# atlas_double.net
KiCad netlist of a schematic drawn in EAGLE
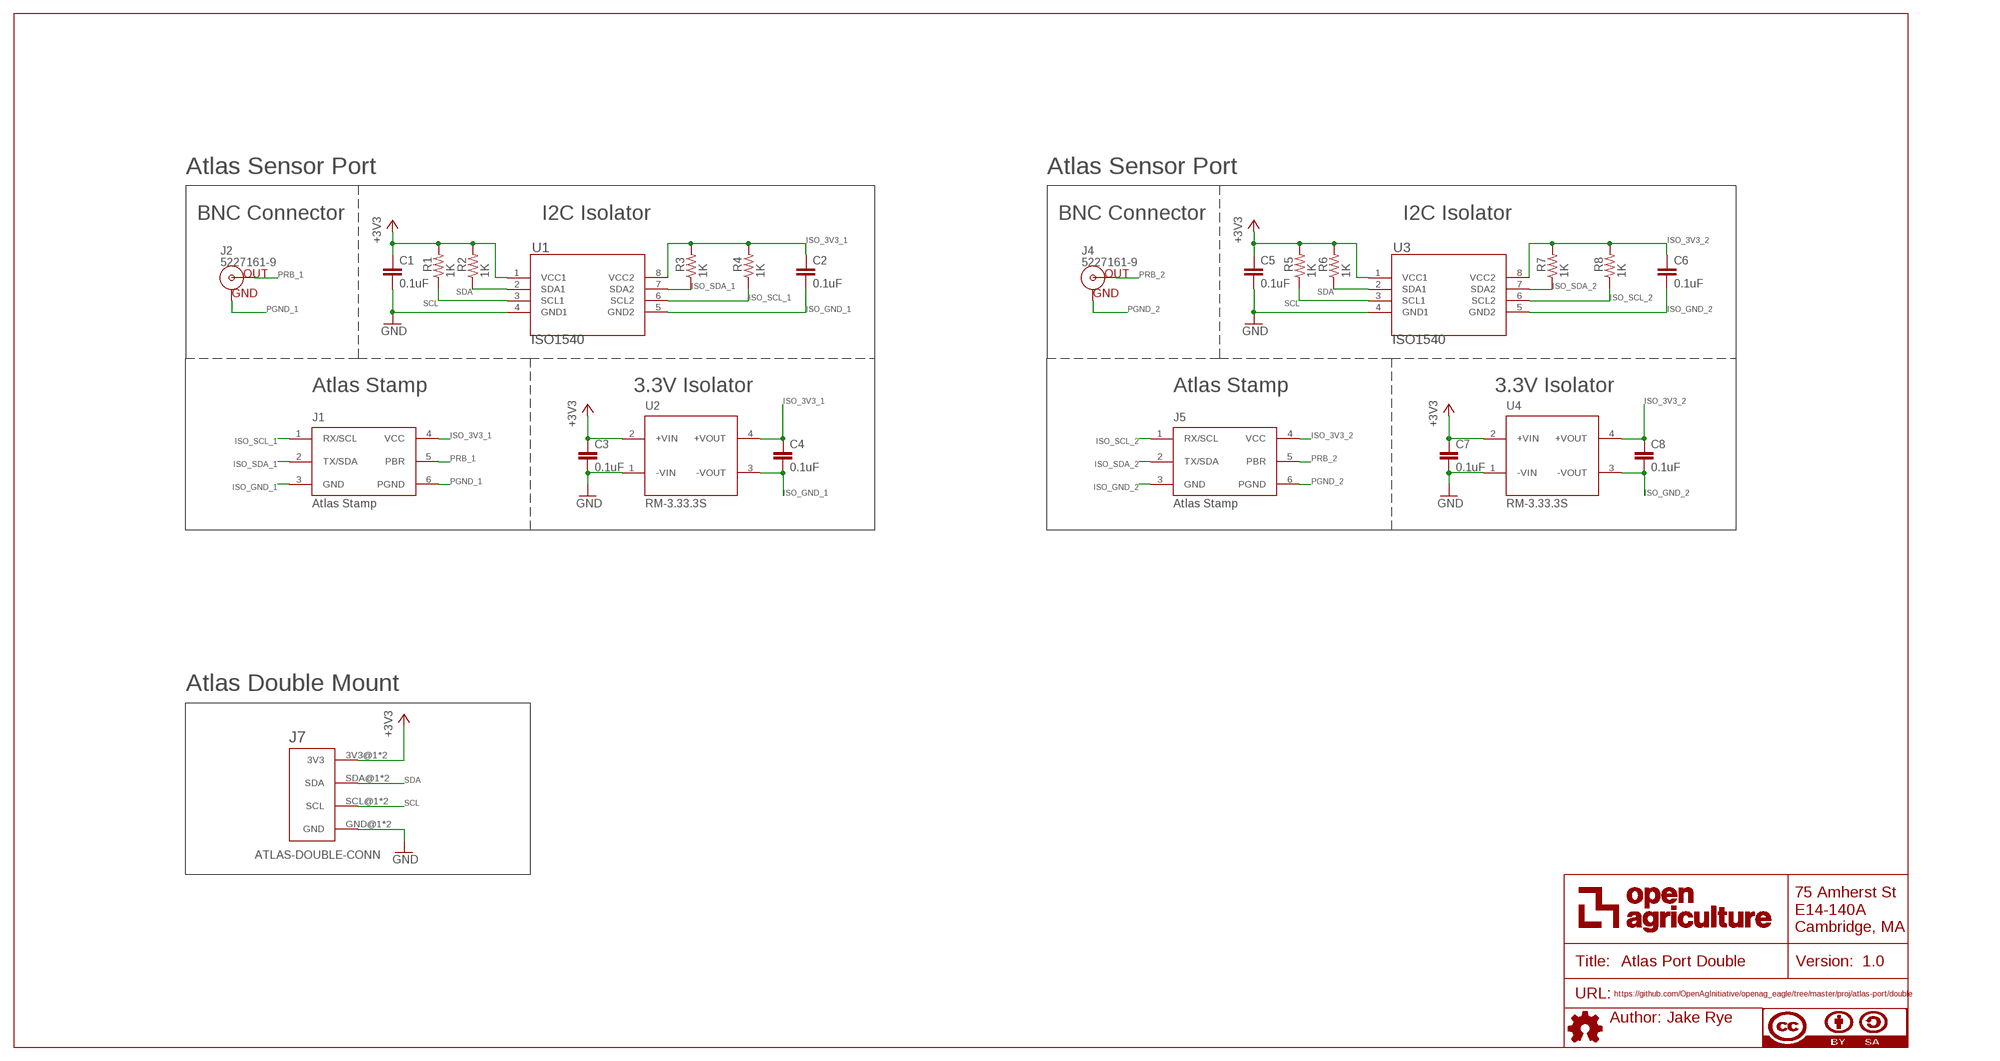
[diagram p0: schematic, sheet 1]

(export (version "E")
  (design (tool "Eeschema 10.0.6"))
  (components
    (comp (ref "C1")
      (value "0.1uF")
      (footprint "eagle-import:C0603")
      (fields (field (name "MANUFACTURER") "Kemet") (field (name "MPN") "C0603C104K5RACTU"))
      (libsource (lib "eagle-import") (part "0.1UF-C0603C104K5RACTU"))
    )
    (comp (ref "C2")
      (value "0.1uF")
      (footprint "eagle-import:C0603")
      (fields (field (name "MANUFACTURER") "Kemet") (field (name "MPN") "C0603C104K5RACTU"))
      (libsource (lib "eagle-import") (part "0.1UF-C0603C104K5RACTU"))
    )
    (comp (ref "C3")
      (value "0.1uF")
      (footprint "eagle-import:C0603")
      (fields (field (name "MANUFACTURER") "Kemet") (field (name "MPN") "C0603C104K5RACTU"))
      (libsource (lib "eagle-import") (part "0.1UF-C0603C104K5RACTU"))
    )
    (comp (ref "C4")
      (value "0.1uF")
      (footprint "eagle-import:C0603")
      (fields (field (name "MANUFACTURER") "Kemet") (field (name "MPN") "C0603C104K5RACTU"))
      (libsource (lib "eagle-import") (part "0.1UF-C0603C104K5RACTU"))
    )
    (comp (ref "C5")
      (value "0.1uF")
      (footprint "eagle-import:C0603")
      (fields (field (name "MANUFACTURER") "Kemet") (field (name "MPN") "C0603C104K5RACTU"))
      (libsource (lib "eagle-import") (part "0.1UF-C0603C104K5RACTU"))
    )
    (comp (ref "C6")
      (value "0.1uF")
      (footprint "eagle-import:C0603")
      (fields (field (name "MANUFACTURER") "Kemet") (field (name "MPN") "C0603C104K5RACTU"))
      (libsource (lib "eagle-import") (part "0.1UF-C0603C104K5RACTU"))
    )
    (comp (ref "C7")
      (value "0.1uF")
      (footprint "eagle-import:C0603")
      (fields (field (name "MANUFACTURER") "Kemet") (field (name "MPN") "C0603C104K5RACTU"))
      (libsource (lib "eagle-import") (part "0.1UF-C0603C104K5RACTU"))
    )
    (comp (ref "C8")
      (value "0.1uF")
      (footprint "eagle-import:C0603")
      (fields (field (name "MANUFACTURER") "Kemet") (field (name "MPN") "C0603C104K5RACTU"))
      (libsource (lib "eagle-import") (part "0.1UF-C0603C104K5RACTU"))
    )
    (comp (ref "J1")
      (value "Atlas Stamp")
      (footprint "eagle-import:ATLAS-STAMP")
      (libsource (lib "eagle-import") (part "ATLAS-STAMP"))
    )
    (comp (ref "J2")
      (value "5227161-9")
      (footprint "eagle-import:BNC-5227161")
      (fields (field (name "MANUFACTURER") "TE Connectivity AMP Connectors"))
      (libsource (lib "eagle-import") (part "BNC-5227161-9PTH"))
    )
    (comp (ref "J4")
      (value "5227161-9")
      (footprint "eagle-import:BNC-5227161")
      (fields (field (name "MANUFACTURER") "TE Connectivity AMP Connectors"))
      (libsource (lib "eagle-import") (part "BNC-5227161-9PTH"))
    )
    (comp (ref "J5")
      (value "Atlas Stamp")
      (footprint "eagle-import:ATLAS-STAMP")
      (libsource (lib "eagle-import") (part "ATLAS-STAMP"))
    )
    (comp (ref "J7")
      (value "ATLAS-DOUBLE-CONN")
      (footprint "eagle-import:ATLAS-DOUBLE")
      (libsource (lib "eagle-import") (part "ATLAS-DOUBLE"))
    )
    (comp (ref "R1")
      (value "1K")
      (footprint "eagle-import:RC0603N")
      (fields (field (name "MANUFACTURER") "Panasonic") (field (name "MPN") "P20283CT-ND"))
      (libsource (lib "eagle-import") (part "1K-ERJ-PB3D1001V"))
    )
    (comp (ref "R2")
      (value "1K")
      (footprint "eagle-import:RC0603N")
      (fields (field (name "MANUFACTURER") "Panasonic") (field (name "MPN") "P20283CT-ND"))
      (libsource (lib "eagle-import") (part "1K-ERJ-PB3D1001V"))
    )
    (comp (ref "R3")
      (value "1K")
      (footprint "eagle-import:RC0603N")
      (fields (field (name "MANUFACTURER") "Panasonic") (field (name "MPN") "P20283CT-ND"))
      (libsource (lib "eagle-import") (part "1K-ERJ-PB3D1001V"))
    )
    (comp (ref "R4")
      (value "1K")
      (footprint "eagle-import:RC0603N")
      (fields (field (name "MANUFACTURER") "Panasonic") (field (name "MPN") "P20283CT-ND"))
      (libsource (lib "eagle-import") (part "1K-ERJ-PB3D1001V"))
    )
    (comp (ref "R5")
      (value "1K")
      (footprint "eagle-import:RC0603N")
      (fields (field (name "MANUFACTURER") "Panasonic") (field (name "MPN") "P20283CT-ND"))
      (libsource (lib "eagle-import") (part "1K-ERJ-PB3D1001V"))
    )
    (comp (ref "R6")
      (value "1K")
      (footprint "eagle-import:RC0603N")
      (fields (field (name "MANUFACTURER") "Panasonic") (field (name "MPN") "P20283CT-ND"))
      (libsource (lib "eagle-import") (part "1K-ERJ-PB3D1001V"))
    )
    (comp (ref "R7")
      (value "1K")
      (footprint "eagle-import:RC0603N")
      (fields (field (name "MANUFACTURER") "Panasonic") (field (name "MPN") "P20283CT-ND"))
      (libsource (lib "eagle-import") (part "1K-ERJ-PB3D1001V"))
    )
    (comp (ref "R8")
      (value "1K")
      (footprint "eagle-import:RC0603N")
      (fields (field (name "MANUFACTURER") "Panasonic") (field (name "MPN") "P20283CT-ND"))
      (libsource (lib "eagle-import") (part "1K-ERJ-PB3D1001V"))
    )
    (comp (ref "U1")
      (value "ISO1540")
      (footprint "eagle-import:D8")
      (fields (field (name "MANUFACTURER") "Texas Instruments") (field (name "MPN") "ISO1540DR"))
      (libsource (lib "eagle-import") (part "ISO1540DR"))
    )
    (comp (ref "U2")
      (value "RM-3.33.3S")
      (footprint "eagle-import:RM3.33.3S-SIP4")
      (fields (field (name "MANUFACTURER") "Recom Power"))
      (libsource (lib "eagle-import") (part "RM3.33.3S"))
    )
    (comp (ref "U3")
      (value "ISO1540")
      (footprint "eagle-import:D8")
      (fields (field (name "MANUFACTURER") "Texas Instruments") (field (name "MPN") "ISO1540DR"))
      (libsource (lib "eagle-import") (part "ISO1540DR"))
    )
    (comp (ref "U4")
      (value "RM-3.33.3S")
      (footprint "eagle-import:RM3.33.3S-SIP4")
      (fields (field (name "MANUFACTURER") "Recom Power"))
      (libsource (lib "eagle-import") (part "RM3.33.3S"))
    )
  )
  (nets
    (net (code "1") (name "+3V3") (class "Default")
      (node (ref "C1") (pin "1") (pinfunction "1_1") (pintype "passive"))
      (node (ref "C3") (pin "1") (pinfunction "1_1") (pintype "passive"))
      (node (ref "C5") (pin "1") (pinfunction "1_1") (pintype "passive"))
      (node (ref "C7") (pin "1") (pinfunction "1_1") (pintype "passive"))
      (node (ref "J7") (pin "3V3@1") (pinfunction "3V3_3V3@1") (pintype "bidirectional"))
      (node (ref "J7") (pin "3V3@2") (pinfunction "3V3_3V3@2") (pintype "bidirectional"))
      (node (ref "R1") (pin "2") (pinfunction "2_2") (pintype "passive"))
      (node (ref "R2") (pin "2") (pinfunction "2_2") (pintype "passive"))
      (node (ref "R5") (pin "2") (pinfunction "2_2") (pintype "passive"))
      (node (ref "R6") (pin "2") (pinfunction "2_2") (pintype "passive"))
      (node (ref "U1") (pin "1") (pinfunction "VCC1_1") (pintype "power_in"))
      (node (ref "U2") (pin "2") (pinfunction "+VIN_2") (pintype "power_in"))
      (node (ref "U3") (pin "1") (pinfunction "VCC1_1") (pintype "power_in"))
      (node (ref "U4") (pin "2") (pinfunction "+VIN_2") (pintype "power_in"))
    )
    (net (code "2") (name "GND") (class "Default")
      (node (ref "C1") (pin "2") (pinfunction "2_2") (pintype "passive"))
      (node (ref "C3") (pin "2") (pinfunction "2_2") (pintype "passive"))
      (node (ref "C5") (pin "2") (pinfunction "2_2") (pintype "passive"))
      (node (ref "C7") (pin "2") (pinfunction "2_2") (pintype "passive"))
      (node (ref "J7") (pin "GND@1") (pinfunction "GND_GND@1") (pintype "bidirectional"))
      (node (ref "J7") (pin "GND@2") (pinfunction "GND_GND@2") (pintype "bidirectional"))
      (node (ref "U1") (pin "4") (pinfunction "GND1_4") (pintype "power_in"))
      (node (ref "U2") (pin "1") (pinfunction "-VIN_1") (pintype "power_in"))
      (node (ref "U3") (pin "4") (pinfunction "GND1_4") (pintype "power_in"))
      (node (ref "U4") (pin "1") (pinfunction "-VIN_1") (pintype "power_in"))
    )
    (net (code "3") (name "ISO_3V3_1") (class "Default")
      (node (ref "C2") (pin "1") (pinfunction "1_1") (pintype "passive"))
      (node (ref "C4") (pin "1") (pinfunction "1_1") (pintype "passive"))
      (node (ref "J1") (pin "4") (pinfunction "VCC_4") (pintype "power_in"))
      (node (ref "R3") (pin "2") (pinfunction "2_2") (pintype "passive"))
      (node (ref "R4") (pin "2") (pinfunction "2_2") (pintype "passive"))
      (node (ref "U1") (pin "8") (pinfunction "VCC2_8") (pintype "power_in"))
      (node (ref "U2") (pin "4") (pinfunction "+VOUT_4") (pintype "power_in"))
    )
    (net (code "4") (name "ISO_3V3_2") (class "Default")
      (node (ref "C6") (pin "1") (pinfunction "1_1") (pintype "passive"))
      (node (ref "C8") (pin "1") (pinfunction "1_1") (pintype "passive"))
      (node (ref "J5") (pin "4") (pinfunction "VCC_4") (pintype "power_in"))
      (node (ref "R7") (pin "2") (pinfunction "2_2") (pintype "passive"))
      (node (ref "R8") (pin "2") (pinfunction "2_2") (pintype "passive"))
      (node (ref "U3") (pin "8") (pinfunction "VCC2_8") (pintype "power_in"))
      (node (ref "U4") (pin "4") (pinfunction "+VOUT_4") (pintype "power_in"))
    )
    (net (code "5") (name "ISO_GND_1") (class "Default")
      (node (ref "C2") (pin "2") (pinfunction "2_2") (pintype "passive"))
      (node (ref "C4") (pin "2") (pinfunction "2_2") (pintype "passive"))
      (node (ref "J1") (pin "3") (pinfunction "GND_3") (pintype "power_in"))
      (node (ref "U1") (pin "5") (pinfunction "GND2_5") (pintype "power_in"))
      (node (ref "U2") (pin "3") (pinfunction "-VOUT_3") (pintype "power_in"))
    )
    (net (code "6") (name "ISO_GND_2") (class "Default")
      (node (ref "C6") (pin "2") (pinfunction "2_2") (pintype "passive"))
      (node (ref "C8") (pin "2") (pinfunction "2_2") (pintype "passive"))
      (node (ref "J5") (pin "3") (pinfunction "GND_3") (pintype "power_in"))
      (node (ref "U3") (pin "5") (pinfunction "GND2_5") (pintype "power_in"))
      (node (ref "U4") (pin "3") (pinfunction "-VOUT_3") (pintype "power_in"))
    )
    (net (code "7") (name "ISO_SCL_1") (class "Default")
      (node (ref "J1") (pin "1") (pinfunction "RX/SCL_1") (pintype "bidirectional"))
      (node (ref "R4") (pin "1") (pinfunction "1_1") (pintype "passive"))
      (node (ref "U1") (pin "6") (pinfunction "SCL2_6") (pintype "bidirectional"))
    )
    (net (code "8") (name "ISO_SCL_2") (class "Default")
      (node (ref "J5") (pin "1") (pinfunction "RX/SCL_1") (pintype "bidirectional"))
      (node (ref "R8") (pin "1") (pinfunction "1_1") (pintype "passive"))
      (node (ref "U3") (pin "6") (pinfunction "SCL2_6") (pintype "bidirectional"))
    )
    (net (code "9") (name "ISO_SDA_1") (class "Default")
      (node (ref "J1") (pin "2") (pinfunction "TX/SDA_2") (pintype "bidirectional"))
      (node (ref "R3") (pin "1") (pinfunction "1_1") (pintype "passive"))
      (node (ref "U1") (pin "7") (pinfunction "SDA2_7") (pintype "bidirectional"))
    )
    (net (code "10") (name "ISO_SDA_2") (class "Default")
      (node (ref "J5") (pin "2") (pinfunction "TX/SDA_2") (pintype "bidirectional"))
      (node (ref "R7") (pin "1") (pinfunction "1_1") (pintype "passive"))
      (node (ref "U3") (pin "7") (pinfunction "SDA2_7") (pintype "bidirectional"))
    )
    (net (code "11") (name "PGND_1") (class "Default")
      (node (ref "J1") (pin "6") (pinfunction "PGND_6") (pintype "power_in"))
      (node (ref "J2") (pin "GND") (pinfunction "GND_GND") (pintype "bidirectional"))
    )
    (net (code "12") (name "PGND_2") (class "Default")
      (node (ref "J4") (pin "GND") (pinfunction "GND_GND") (pintype "bidirectional"))
      (node (ref "J5") (pin "6") (pinfunction "PGND_6") (pintype "power_in"))
    )
    (net (code "13") (name "PRB_1") (class "Default")
      (node (ref "J1") (pin "5") (pinfunction "PBR_5") (pintype "bidirectional"))
      (node (ref "J2") (pin "S") (pinfunction "OUT_S") (pintype "bidirectional"))
    )
    (net (code "14") (name "PRB_2") (class "Default")
      (node (ref "J4") (pin "S") (pinfunction "OUT_S") (pintype "bidirectional"))
      (node (ref "J5") (pin "5") (pinfunction "PBR_5") (pintype "bidirectional"))
    )
    (net (code "15") (name "SCL") (class "Default")
      (node (ref "J7") (pin "SCL@1") (pinfunction "SCL_SCL@1") (pintype "bidirectional"))
      (node (ref "J7") (pin "SCL@2") (pinfunction "SCL_SCL@2") (pintype "bidirectional"))
      (node (ref "R1") (pin "1") (pinfunction "1_1") (pintype "passive"))
      (node (ref "R5") (pin "1") (pinfunction "1_1") (pintype "passive"))
      (node (ref "U1") (pin "3") (pinfunction "SCL1_3") (pintype "bidirectional"))
      (node (ref "U3") (pin "3") (pinfunction "SCL1_3") (pintype "bidirectional"))
    )
    (net (code "16") (name "SDA") (class "Default")
      (node (ref "J7") (pin "SDA@1") (pinfunction "SDA_SDA@1") (pintype "bidirectional"))
      (node (ref "J7") (pin "SDA@2") (pinfunction "SDA_SDA@2") (pintype "bidirectional"))
      (node (ref "R2") (pin "1") (pinfunction "1_1") (pintype "passive"))
      (node (ref "R6") (pin "1") (pinfunction "1_1") (pintype "passive"))
      (node (ref "U1") (pin "2") (pinfunction "SDA1_2") (pintype "bidirectional"))
      (node (ref "U3") (pin "2") (pinfunction "SDA1_2") (pintype "bidirectional"))
    )
  )
)
